# Muxes_and_ADC.net
KiCad netlist of a schematic drawn in Altium Designer
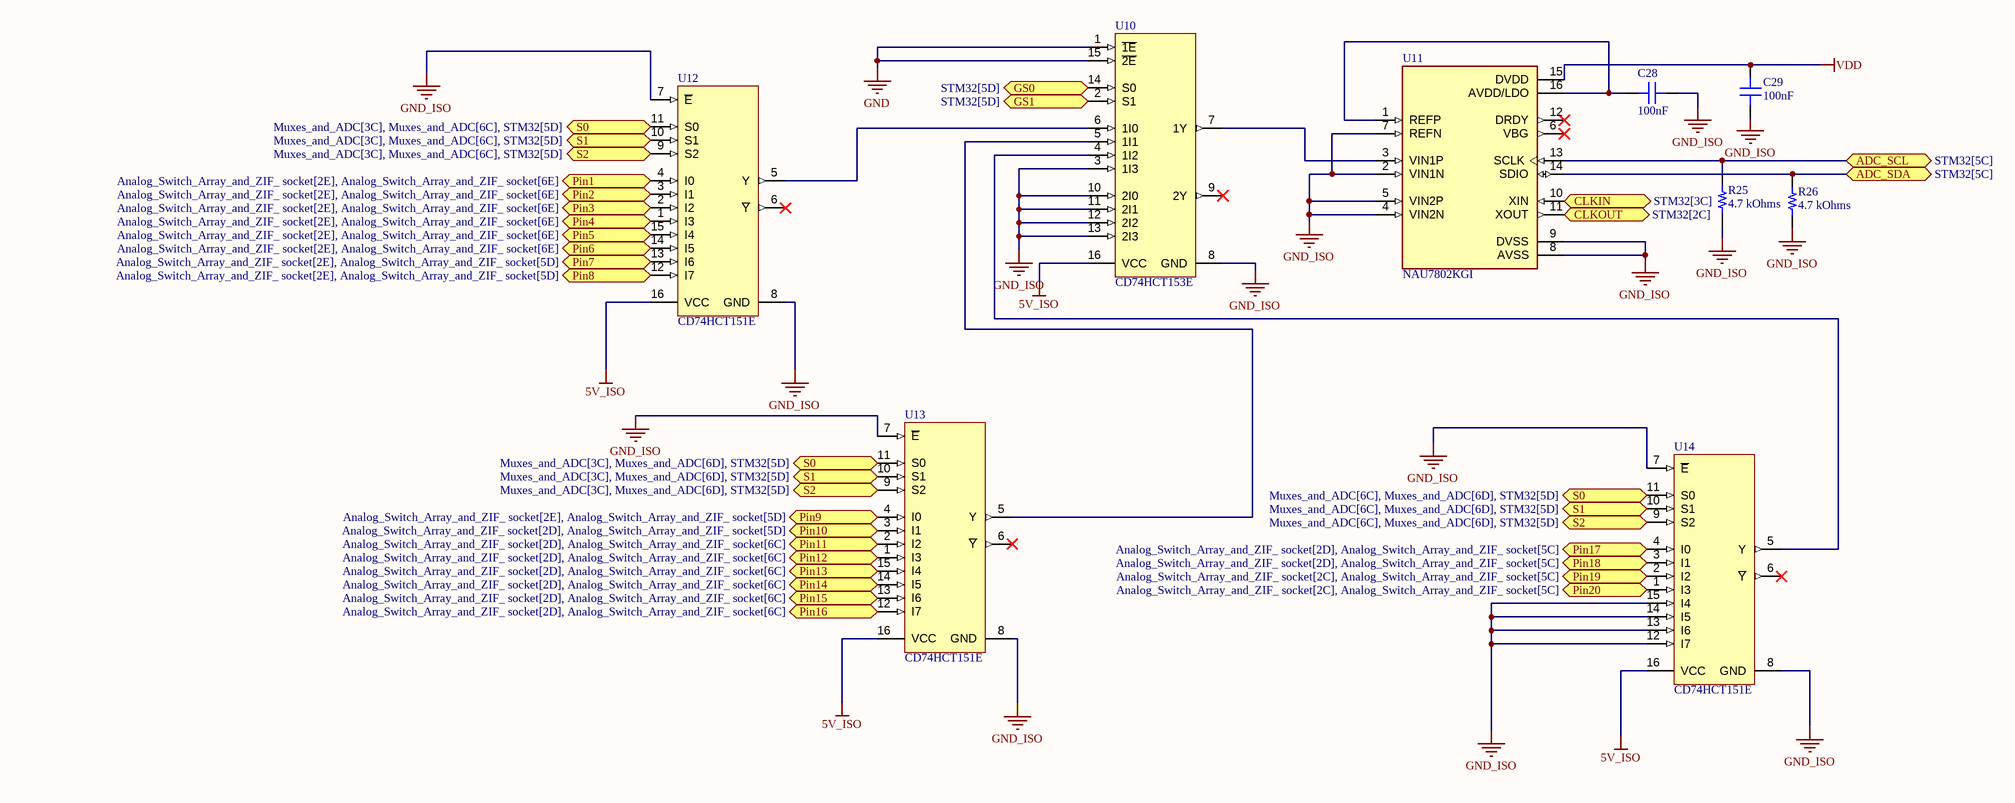
[diagram p0: Muxes_and_ADC.SchDoc]

(export (version "E")
  (design (tool "Eeschema 10.0.6"))
  (components
    (comp (ref "C28")
      (value "100nF")
      (footprint "CAP 1206_3216 - 0.8MM")
      (description "CAP CER 1206 0.1F 16V ULTRA STAB")
      (fields (field (name "PART NUMBER") "C1206X104G4HAC7800"))
      (libsource (lib "University of Massachusetts Lowell") (part "CAPACITOR"))
    )
    (comp (ref "C29")
      (value "100nF")
      (footprint "CAP 1206_3216 - 0.8MM")
      (description "CAP CER 1206 0.1F 16V ULTRA STAB")
      (fields (field (name "PART NUMBER") "C1206X104G4HAC7800"))
      (libsource (lib "University of Massachusetts Lowell") (part "CAPACITOR"))
    )
    (comp (ref "R25")
      (value "4.7 kOhms")
      (footprint "RES 0603_1608")
      (description "RES SMD 4.7K OHM 1% 1/10W 0603")
      (fields (field (name "PART NUMBER") "KTR03EZPF4701"))
      (libsource (lib "University of Massachusetts Lowell") (part "RESISTOR"))
    )
    (comp (ref "R26")
      (value "4.7 kOhms")
      (footprint "RES 0603_1608")
      (description "RES SMD 4.7K OHM 1% 1/10W 0603")
      (fields (field (name "PART NUMBER") "KTR03EZPF4701"))
      (libsource (lib "University of Massachusetts Lowell") (part "RESISTOR"))
    )
    (comp (ref "U10")
      (value "CD74HCT153E")
      (footprint "N0016A")
      (description "High Speed CMOS Logic Dual 4-Input Multiplexers, N0016A, TUBE")
      (fields
        (field (name "MANUFACTURER") "Texas Instruments")
        (field (name "GENERIC PART NUMBER") "CD74HCT153")
      )
      (libsource (lib "Altium Content Vault") (part "TI-CD54_74HCX153-16"))
    )
    (comp (ref "U11")
      (value "NAU7802KGI")
      (footprint "DIP792W45P254L1904H533Q16")
      (description "24 Bit Analog to Digital Converter 2 Input 1 Sigma-Delta 16-PDIP")
      (fields (field (name "MF") "Nuvoton Technology Corporation of America"))
      (libsource (lib "University of Massachusetts Lowell") (part "NAU7802KGI"))
    )
    (comp (ref "U12")
      (value "CD74HCT151E")
      (footprint "N0016A")
      (description "High Speed CMOS Logic 8-Input Multiplexer, N0016A, TUBE")
      (fields
        (field (name "MANUFACTURER") "Texas Instruments")
        (field (name "GENERIC PART NUMBER") "CD74HCT151")
      )
      (libsource (lib "Altium Content Vault") (part "TI-CDX4HCX151-16"))
    )
    (comp (ref "U13")
      (value "CD74HCT151E")
      (footprint "N0016A")
      (description "High Speed CMOS Logic 8-Input Multiplexer, N0016A, TUBE")
      (fields
        (field (name "MANUFACTURER") "Texas Instruments")
        (field (name "GENERIC PART NUMBER") "CD74HCT151")
      )
      (libsource (lib "Altium Content Vault") (part "TI-CDX4HCX151-16"))
    )
    (comp (ref "U14")
      (value "CD74HCT151E")
      (footprint "N0016A")
      (description "High Speed CMOS Logic 8-Input Multiplexer, N0016A, TUBE")
      (fields
        (field (name "MANUFACTURER") "Texas Instruments")
        (field (name "GENERIC PART NUMBER") "CD74HCT151")
      )
      (libsource (lib "Altium Content Vault") (part "TI-CDX4HCX151-16"))
    )
  )
  (nets
    (net (code "1") (name "/ADC_SCL") (class "Default")
      (node (ref "R25") (pin "2") (pinfunction "2_2") (pintype "passive"))
      (node (ref "U11") (pin "13") (pinfunction "SCLK_13") (pintype "input"))
    )
    (net (code "2") (name "/ADC_SDA") (class "Default")
      (node (ref "R26") (pin "2") (pinfunction "2_2") (pintype "passive"))
      (node (ref "U11") (pin "14") (pinfunction "SDIO_14") (pintype "bidirectional"))
    )
    (net (code "3") (name "/CLKIN") (class "Default")
      (node (ref "U11") (pin "10") (pinfunction "XIN_10") (pintype "input"))
    )
    (net (code "4") (name "/CLKOUT") (class "Default")
      (node (ref "U11") (pin "11") (pinfunction "XOUT_11") (pintype "output"))
    )
    (net (code "5") (name "/GS0") (class "Default")
      (node (ref "U10") (pin "14") (pinfunction "S0_14") (pintype "input"))
    )
    (net (code "6") (name "/GS1") (class "Default")
      (node (ref "U10") (pin "2") (pinfunction "S1_2") (pintype "input"))
    )
    (net (code "7") (name "/Pin1") (class "Default")
      (node (ref "U12") (pin "4") (pinfunction "I0_4") (pintype "input"))
    )
    (net (code "8") (name "/Pin2") (class "Default")
      (node (ref "U12") (pin "3") (pinfunction "I1_3") (pintype "input"))
    )
    (net (code "9") (name "/Pin3") (class "Default")
      (node (ref "U12") (pin "2") (pinfunction "I2_2") (pintype "input"))
    )
    (net (code "10") (name "/Pin4") (class "Default")
      (node (ref "U12") (pin "1") (pinfunction "I3_1") (pintype "input"))
    )
    (net (code "11") (name "/Pin5") (class "Default")
      (node (ref "U12") (pin "15") (pinfunction "I4_15") (pintype "input"))
    )
    (net (code "12") (name "/Pin6") (class "Default")
      (node (ref "U12") (pin "14") (pinfunction "I5_14") (pintype "input"))
    )
    (net (code "13") (name "/Pin7") (class "Default")
      (node (ref "U12") (pin "13") (pinfunction "I6_13") (pintype "input"))
    )
    (net (code "14") (name "/Pin8") (class "Default")
      (node (ref "U12") (pin "12") (pinfunction "I7_12") (pintype "input"))
    )
    (net (code "15") (name "/Pin9") (class "Default")
      (node (ref "U13") (pin "4") (pinfunction "I0_4") (pintype "input"))
    )
    (net (code "16") (name "/Pin10") (class "Default")
      (node (ref "U13") (pin "3") (pinfunction "I1_3") (pintype "input"))
    )
    (net (code "17") (name "/Pin11") (class "Default")
      (node (ref "U13") (pin "2") (pinfunction "I2_2") (pintype "input"))
    )
    (net (code "18") (name "/Pin12") (class "Default")
      (node (ref "U13") (pin "1") (pinfunction "I3_1") (pintype "input"))
    )
    (net (code "19") (name "/Pin13") (class "Default")
      (node (ref "U13") (pin "15") (pinfunction "I4_15") (pintype "input"))
    )
    (net (code "20") (name "/Pin14") (class "Default")
      (node (ref "U13") (pin "14") (pinfunction "I5_14") (pintype "input"))
    )
    (net (code "21") (name "/Pin15") (class "Default")
      (node (ref "U13") (pin "13") (pinfunction "I6_13") (pintype "input"))
    )
    (net (code "22") (name "/Pin16") (class "Default")
      (node (ref "U13") (pin "12") (pinfunction "I7_12") (pintype "input"))
    )
    (net (code "23") (name "/Pin17") (class "Default")
      (node (ref "U14") (pin "4") (pinfunction "I0_4") (pintype "input"))
    )
    (net (code "24") (name "/Pin18") (class "Default")
      (node (ref "U14") (pin "3") (pinfunction "I1_3") (pintype "input"))
    )
    (net (code "25") (name "/Pin19") (class "Default")
      (node (ref "U14") (pin "2") (pinfunction "I2_2") (pintype "input"))
    )
    (net (code "26") (name "/Pin20") (class "Default")
      (node (ref "U14") (pin "1") (pinfunction "I3_1") (pintype "input"))
    )
    (net (code "27") (name "/S0") (class "Default")
      (node (ref "U12") (pin "11") (pinfunction "S0_11") (pintype "input"))
      (node (ref "U13") (pin "11") (pinfunction "S0_11") (pintype "input"))
      (node (ref "U14") (pin "11") (pinfunction "S0_11") (pintype "input"))
    )
    (net (code "28") (name "/S1") (class "Default")
      (node (ref "U12") (pin "10") (pinfunction "S1_10") (pintype "input"))
      (node (ref "U13") (pin "10") (pinfunction "S1_10") (pintype "input"))
      (node (ref "U14") (pin "10") (pinfunction "S1_10") (pintype "input"))
    )
    (net (code "29") (name "/S2") (class "Default")
      (node (ref "U12") (pin "9") (pinfunction "S2_9") (pintype "input"))
      (node (ref "U13") (pin "9") (pinfunction "S2_9") (pintype "input"))
      (node (ref "U14") (pin "9") (pinfunction "S2_9") (pintype "input"))
    )
    (net (code "30") (name "5V_ISO") (class "Default")
      (node (ref "U10") (pin "16") (pinfunction "VCC_16") (pintype "power_in"))
      (node (ref "U12") (pin "16") (pinfunction "VCC_16") (pintype "power_in"))
      (node (ref "U13") (pin "16") (pinfunction "VCC_16") (pintype "power_in"))
      (node (ref "U14") (pin "16") (pinfunction "VCC_16") (pintype "power_in"))
    )
    (net (code "31") (name "GND") (class "Default")
      (node (ref "U10") (pin "1") (pinfunction "~{1E}_1") (pintype "input"))
      (node (ref "U10") (pin "15") (pinfunction "~{2E}_15") (pintype "input"))
    )
    (net (code "32") (name "GND_ISO") (class "Default")
      (node (ref "C28") (pin "1") (pinfunction "1_1") (pintype "passive"))
      (node (ref "C29") (pin "2") (pinfunction "2_2") (pintype "passive"))
      (node (ref "R25") (pin "1") (pinfunction "1_1") (pintype "passive"))
      (node (ref "R26") (pin "1") (pinfunction "1_1") (pintype "passive"))
      (node (ref "U10") (pin "10") (pinfunction "2I0_10") (pintype "input"))
      (node (ref "U10") (pin "11") (pinfunction "2I1_11") (pintype "input"))
      (node (ref "U10") (pin "12") (pinfunction "2I2_12") (pintype "input"))
      (node (ref "U10") (pin "13") (pinfunction "2I3_13") (pintype "input"))
      (node (ref "U10") (pin "3") (pinfunction "1I3_3") (pintype "input"))
      (node (ref "U10") (pin "8") (pinfunction "GND_8") (pintype "power_in"))
      (node (ref "U11") (pin "2") (pinfunction "VIN1N_2") (pintype "input"))
      (node (ref "U11") (pin "4") (pinfunction "VIN2N_4") (pintype "input"))
      (node (ref "U11") (pin "5") (pinfunction "VIN2P_5") (pintype "input"))
      (node (ref "U11") (pin "7") (pinfunction "REFN_7") (pintype "input"))
      (node (ref "U11") (pin "8") (pinfunction "AVSS_8") (pintype "power_in"))
      (node (ref "U11") (pin "9") (pinfunction "DVSS_9") (pintype "power_in"))
      (node (ref "U12") (pin "7") (pinfunction "~{E}_7") (pintype "input"))
      (node (ref "U12") (pin "8") (pinfunction "GND_8") (pintype "power_in"))
      (node (ref "U13") (pin "7") (pinfunction "~{E}_7") (pintype "input"))
      (node (ref "U13") (pin "8") (pinfunction "GND_8") (pintype "power_in"))
      (node (ref "U14") (pin "12") (pinfunction "I7_12") (pintype "input"))
      (node (ref "U14") (pin "13") (pinfunction "I6_13") (pintype "input"))
      (node (ref "U14") (pin "14") (pinfunction "I5_14") (pintype "input"))
      (node (ref "U14") (pin "15") (pinfunction "I4_15") (pintype "input"))
      (node (ref "U14") (pin "7") (pinfunction "~{E}_7") (pintype "input"))
      (node (ref "U14") (pin "8") (pinfunction "GND_8") (pintype "power_in"))
    )
    (net (code "33") (name "Net-(U10-1I0)") (class "Default")
      (node (ref "U10") (pin "6") (pinfunction "1I0_6") (pintype "input"))
      (node (ref "U12") (pin "5") (pinfunction "Y_5") (pintype "output"))
    )
    (net (code "34") (name "Net-(U10-1I1)") (class "Default")
      (node (ref "U10") (pin "5") (pinfunction "1I1_5") (pintype "input"))
      (node (ref "U13") (pin "5") (pinfunction "Y_5") (pintype "output"))
    )
    (net (code "35") (name "Net-(U10-1I2)") (class "Default")
      (node (ref "U10") (pin "4") (pinfunction "1I2_4") (pintype "input"))
      (node (ref "U14") (pin "5") (pinfunction "Y_5") (pintype "output"))
    )
    (net (code "36") (name "Net-(U10-1Y)") (class "Default")
      (node (ref "U10") (pin "7") (pinfunction "1Y_7") (pintype "output"))
      (node (ref "U11") (pin "3") (pinfunction "VIN1P_3") (pintype "input"))
    )
    (net (code "37") (name "Net-(U11-AVDD{slash}LDO)") (class "Default")
      (node (ref "C28") (pin "2") (pinfunction "2_2") (pintype "passive"))
      (node (ref "U11") (pin "1") (pinfunction "REFP_1") (pintype "input"))
      (node (ref "U11") (pin "16") (pinfunction "AVDD/LDO_16") (pintype "power_in"))
    )
    (net (code "38") (name "VDD") (class "Default")
      (node (ref "C29") (pin "1") (pinfunction "1_1") (pintype "passive"))
      (node (ref "U11") (pin "15") (pinfunction "DVDD_15") (pintype "power_in"))
    )
    (net (code "39") (name "unconnected-(U10-2Y-Pad9)") (class "Default")
      (node (ref "U10") (pin "9") (pinfunction "2Y_9") (pintype "output+no_connect"))
    )
    (net (code "40") (name "unconnected-(U11-DRDY-Pad12)") (class "Default")
      (node (ref "U11") (pin "12") (pinfunction "DRDY_12") (pintype "output+no_connect"))
    )
    (net (code "41") (name "unconnected-(U11-VBG-Pad6)") (class "Default")
      (node (ref "U11") (pin "6") (pinfunction "VBG_6") (pintype "output+no_connect"))
    )
    (net (code "42") (name "unconnected-(U12-~{Y}-Pad6)") (class "Default")
      (node (ref "U12") (pin "6") (pinfunction "~{Y}_6") (pintype "output+no_connect"))
    )
    (net (code "43") (name "unconnected-(U13-~{Y}-Pad6)") (class "Default")
      (node (ref "U13") (pin "6") (pinfunction "~{Y}_6") (pintype "output+no_connect"))
    )
    (net (code "44") (name "unconnected-(U14-~{Y}-Pad6)") (class "Default")
      (node (ref "U14") (pin "6") (pinfunction "~{Y}_6") (pintype "output+no_connect"))
    )
  )
)
